# Power_Supply_Circuit.net
KiCad netlist of a schematic drawn in EAGLE
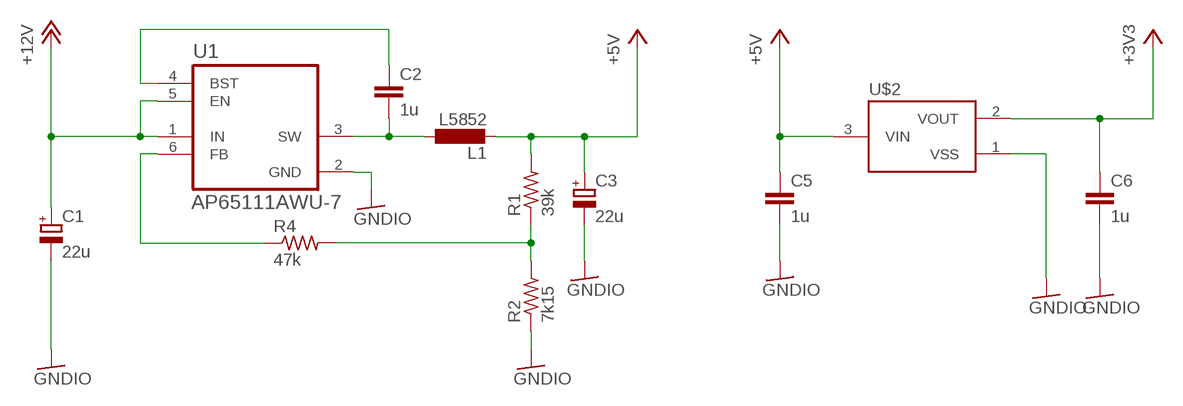
[diagram p0: schematic, sheet 1]

(export (version "E")
  (design (tool "Eeschema 10.0.6"))
  (components
    (comp (ref "C1")
      (value "22u")
      (footprint "eagle-import:E2-5")
      (libsource (lib "eagle-import") (part "CPOL-EUE2-5"))
    )
    (comp (ref "C2")
      (value "1u")
      (footprint "eagle-import:C0603")
      (libsource (lib "eagle-import") (part "C-EUC0603"))
    )
    (comp (ref "C3")
      (value "22u")
      (footprint "eagle-import:E2-5")
      (libsource (lib "eagle-import") (part "CPOL-EUE2-5"))
    )
    (comp (ref "C5")
      (value "1u")
      (footprint "eagle-import:C0603")
      (libsource (lib "eagle-import") (part "C-EUC0603"))
    )
    (comp (ref "C6")
      (value "1u")
      (footprint "eagle-import:C0603")
      (libsource (lib "eagle-import") (part "C-EUC0603"))
    )
    (comp (ref "L1")
      (value "L5852")
      (footprint "eagle-import:L5852")
      (libsource (lib "eagle-import") (part "L5852"))
    )
    (comp (ref "R1")
      (value "39k")
      (footprint "eagle-import:R0603")
      (libsource (lib "eagle-import") (part "R-US_R0603"))
    )
    (comp (ref "R2")
      (value "7k15")
      (footprint "eagle-import:R0603")
      (libsource (lib "eagle-import") (part "R-US_R0603"))
    )
    (comp (ref "R4")
      (value "47k")
      (footprint "eagle-import:R0603")
      (libsource (lib "eagle-import") (part "R-US_R0603"))
    )
    (comp (ref "U$2")
      (value "AP2120")
      (footprint "eagle-import:SOT95P240X110-3")
      (libsource (lib "eagle-import") (part "AP2120"))
    )
    (comp (ref "U1")
      (value "AP65111AWU-7")
      (footprint "eagle-import:SOT95P280X100-6N")
      (fields (field (name "DIGI-KEY_PART_NUMBER") "AP65111AWU-7DICT-ND") (field (name "MF") "Diodes Inc."))
      (libsource (lib "eagle-import") (part "AP65111AWU-7"))
    )
  )
  (nets
    (net (code "1") (name "+3V3") (class "Default")
      (node (ref "C6") (pin "1") (pinfunction "1_1") (pintype "passive"))
      (node (ref "U$2") (pin "2") (pinfunction "VOUT_2") (pintype "bidirectional"))
    )
    (net (code "2") (name "+5V") (class "Default")
      (node (ref "C3") (pin "+") (pinfunction "+_+") (pintype "passive"))
      (node (ref "C5") (pin "1") (pinfunction "1_1") (pintype "passive"))
      (node (ref "L1") (pin "P$2") (pinfunction "2_P$2") (pintype "passive"))
      (node (ref "R1") (pin "2") (pinfunction "2_2") (pintype "passive"))
      (node (ref "U$2") (pin "3") (pinfunction "VIN_3") (pintype "bidirectional"))
    )
    (net (code "3") (name "+12V") (class "Default")
      (node (ref "C1") (pin "+") (pinfunction "+_+") (pintype "passive"))
      (node (ref "U1") (pin "1") (pinfunction "IN_1") (pintype "input"))
      (node (ref "U1") (pin "5") (pinfunction "EN_5") (pintype "input"))
    )
    (net (code "4") (name "GNDIO") (class "Default")
      (node (ref "C1") (pin "-") (pinfunction "-_-") (pintype "passive"))
      (node (ref "C3") (pin "-") (pinfunction "-_-") (pintype "passive"))
      (node (ref "C5") (pin "2") (pinfunction "2_2") (pintype "passive"))
      (node (ref "C6") (pin "2") (pinfunction "2_2") (pintype "passive"))
      (node (ref "R2") (pin "1") (pinfunction "1_1") (pintype "passive"))
      (node (ref "U$2") (pin "1") (pinfunction "VSS_1") (pintype "bidirectional"))
      (node (ref "U1") (pin "2") (pinfunction "GND_2") (pintype "power_in"))
    )
    (net (code "5") (name "Net-(L1-1)") (class "Default")
      (node (ref "C2") (pin "2") (pinfunction "2_2") (pintype "passive"))
      (node (ref "L1") (pin "P$1") (pinfunction "1_P$1") (pintype "passive"))
      (node (ref "U1") (pin "3") (pinfunction "SW_3") (pintype "output"))
    )
    (net (code "6") (name "Net-(R1-Pad1)") (class "Default")
      (node (ref "R1") (pin "1") (pinfunction "1_1") (pintype "passive"))
      (node (ref "R2") (pin "2") (pinfunction "2_2") (pintype "passive"))
      (node (ref "R4") (pin "2") (pinfunction "2_2") (pintype "passive"))
    )
    (net (code "7") (name "Net-(U1-BST)") (class "Default")
      (node (ref "C2") (pin "1") (pinfunction "1_1") (pintype "passive"))
      (node (ref "U1") (pin "4") (pinfunction "BST_4") (pintype "input"))
    )
    (net (code "8") (name "Net-(U1-FB)") (class "Default")
      (node (ref "R4") (pin "1") (pinfunction "1_1") (pintype "passive"))
      (node (ref "U1") (pin "6") (pinfunction "FB_6") (pintype "input"))
    )
  )
)
